# I2C_P_Sensor.net
KiCad netlist of a schematic drawn in Altium Designer
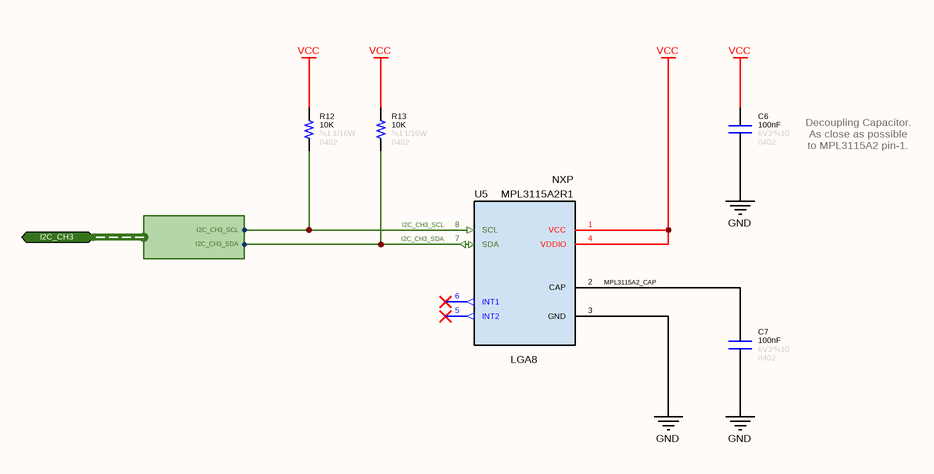
[diagram p0: I2C P Sensor.SchDoc]

(export (version "E")
  (design (tool "Eeschema 10.0.6"))
  (components
    (comp (ref "C6")
      (value "100nF")
      (footprint "CAPACITOR_0402")
      (description "Capacitor - 100nF [0402-6V3] (Ceramic)")
      (fields
        (field (name "MANUFACTURER PART NUMBER") "04026D104KAT4A")
        (field (name "TOLERANCE") "%10")
        (field (name "VOLTAGE") "6V3")
        (field (name "CASE") "0402")
        (field (name "Comment") "Capacitor - 100nF [0402] (Ceramic)")
      )
      (libsource (lib "P101DA_Library") (part "Capacitor - 100nF [0402-6V3]"))
    )
    (comp (ref "C7")
      (value "100nF")
      (footprint "CAPACITOR_0402")
      (description "Capacitor - 100nF [0402-6V3] (Ceramic)")
      (fields
        (field (name "MANUFACTURER PART NUMBER") "04026D104KAT4A")
        (field (name "TOLERANCE") "%10")
        (field (name "VOLTAGE") "6V3")
        (field (name "CASE") "0402")
        (field (name "Comment") "Capacitor - 100nF [0402] (Ceramic)")
      )
      (libsource (lib "P101DA_Library") (part "Capacitor - 100nF [0402-6V3]"))
    )
    (comp (ref "R12")
      (value "10K")
      (footprint "RESISTOR_0402")
      (description "Thick Film Resistors - SMD 1/16 W 10 KOhm 1%")
      (fields
        (field (name "MANUFACTURER PART NUMBER") "CRCW040210K0FKED")
        (field (name "TOLERANCE") "%1")
        (field (name "CASE") "0402")
        (field (name "POWER") "1/16W")
        (field (name "Comment") "10K - 0402 - %1 - 1/16W")
      )
      (libsource (lib "P101DA_Library") (part "Resistor - 10K [0402]"))
    )
    (comp (ref "R13")
      (value "10K")
      (footprint "RESISTOR_0402")
      (description "Thick Film Resistors - SMD 1/16 W 10 KOhm 1%")
      (fields
        (field (name "MANUFACTURER PART NUMBER") "CRCW040210K0FKED")
        (field (name "TOLERANCE") "%1")
        (field (name "CASE") "0402")
        (field (name "POWER") "1/16W")
        (field (name "Comment") "10K - 0402 - %1 - 1/16W")
      )
      (libsource (lib "P101DA_Library") (part "Resistor - 10K [0402]"))
    )
    (comp (ref "U5")
      (value "MPL3115A2R1")
      (footprint "MPL3115A2")
      (description "Board Mount Pressure Sensors")
      (fields
        (field (name "MANUFACTURER NAME") "NXP")
        (field (name "MANUFACTURER PART NUMBER") "MPL3115A2R1")
        (field (name "CASE") "LGA8")
      )
      (libsource (lib "P101DA_Library") (part "IC - MPL3115A2R1"))
    )
  )
  (nets
    (net (code "2") (name "/I2C_CH3_SCL") (class "Default")
      (node (ref "R12") (pin "1") (pinfunction "1_1") (pintype "passive"))
      (node (ref "U5") (pin "8") (pinfunction "SCL_8") (pintype "input"))
    )
    (net (code "3") (name "/I2C_CH3_SDA") (class "Default")
      (node (ref "R13") (pin "1") (pinfunction "1_1") (pintype "passive"))
      (node (ref "U5") (pin "7") (pinfunction "SDA_7") (pintype "bidirectional"))
    )
    (net (code "4") (name "/MPL3115A2_CAP") (class "Default")
      (node (ref "C7") (pin "2") (pinfunction "2_2") (pintype "passive"))
      (node (ref "U5") (pin "2") (pinfunction "CAP_2") (pintype "passive"))
    )
    (net (code "6") (name "GND") (class "Default")
      (node (ref "C6") (pin "1") (pinfunction "1_1") (pintype "passive"))
      (node (ref "C7") (pin "1") (pinfunction "1_1") (pintype "passive"))
      (node (ref "U5") (pin "3") (pinfunction "GND_3") (pintype "power_in"))
    )
    (net (code "7") (name "VCC") (class "Default")
      (node (ref "C6") (pin "2") (pinfunction "2_2") (pintype "passive"))
      (node (ref "R12") (pin "2") (pinfunction "2_2") (pintype "passive"))
      (node (ref "R13") (pin "2") (pinfunction "2_2") (pintype "passive"))
      (node (ref "U5") (pin "1") (pinfunction "VCC_1") (pintype "power_in"))
      (node (ref "U5") (pin "4") (pinfunction "VDDIO_4") (pintype "power_in"))
    )
    (net (code "8") (name "unconnected-(U5-INT1-Pad6)") (class "Default")
      (node (ref "U5") (pin "6") (pinfunction "INT1_6") (pintype "output+no_connect"))
    )
    (net (code "9") (name "unconnected-(U5-INT2-Pad5)") (class "Default")
      (node (ref "U5") (pin "5") (pinfunction "INT2_5") (pintype "output+no_connect"))
    )
  )
)
